# usb-cable.net
KiCad netlist of a schematic drawn in EAGLE
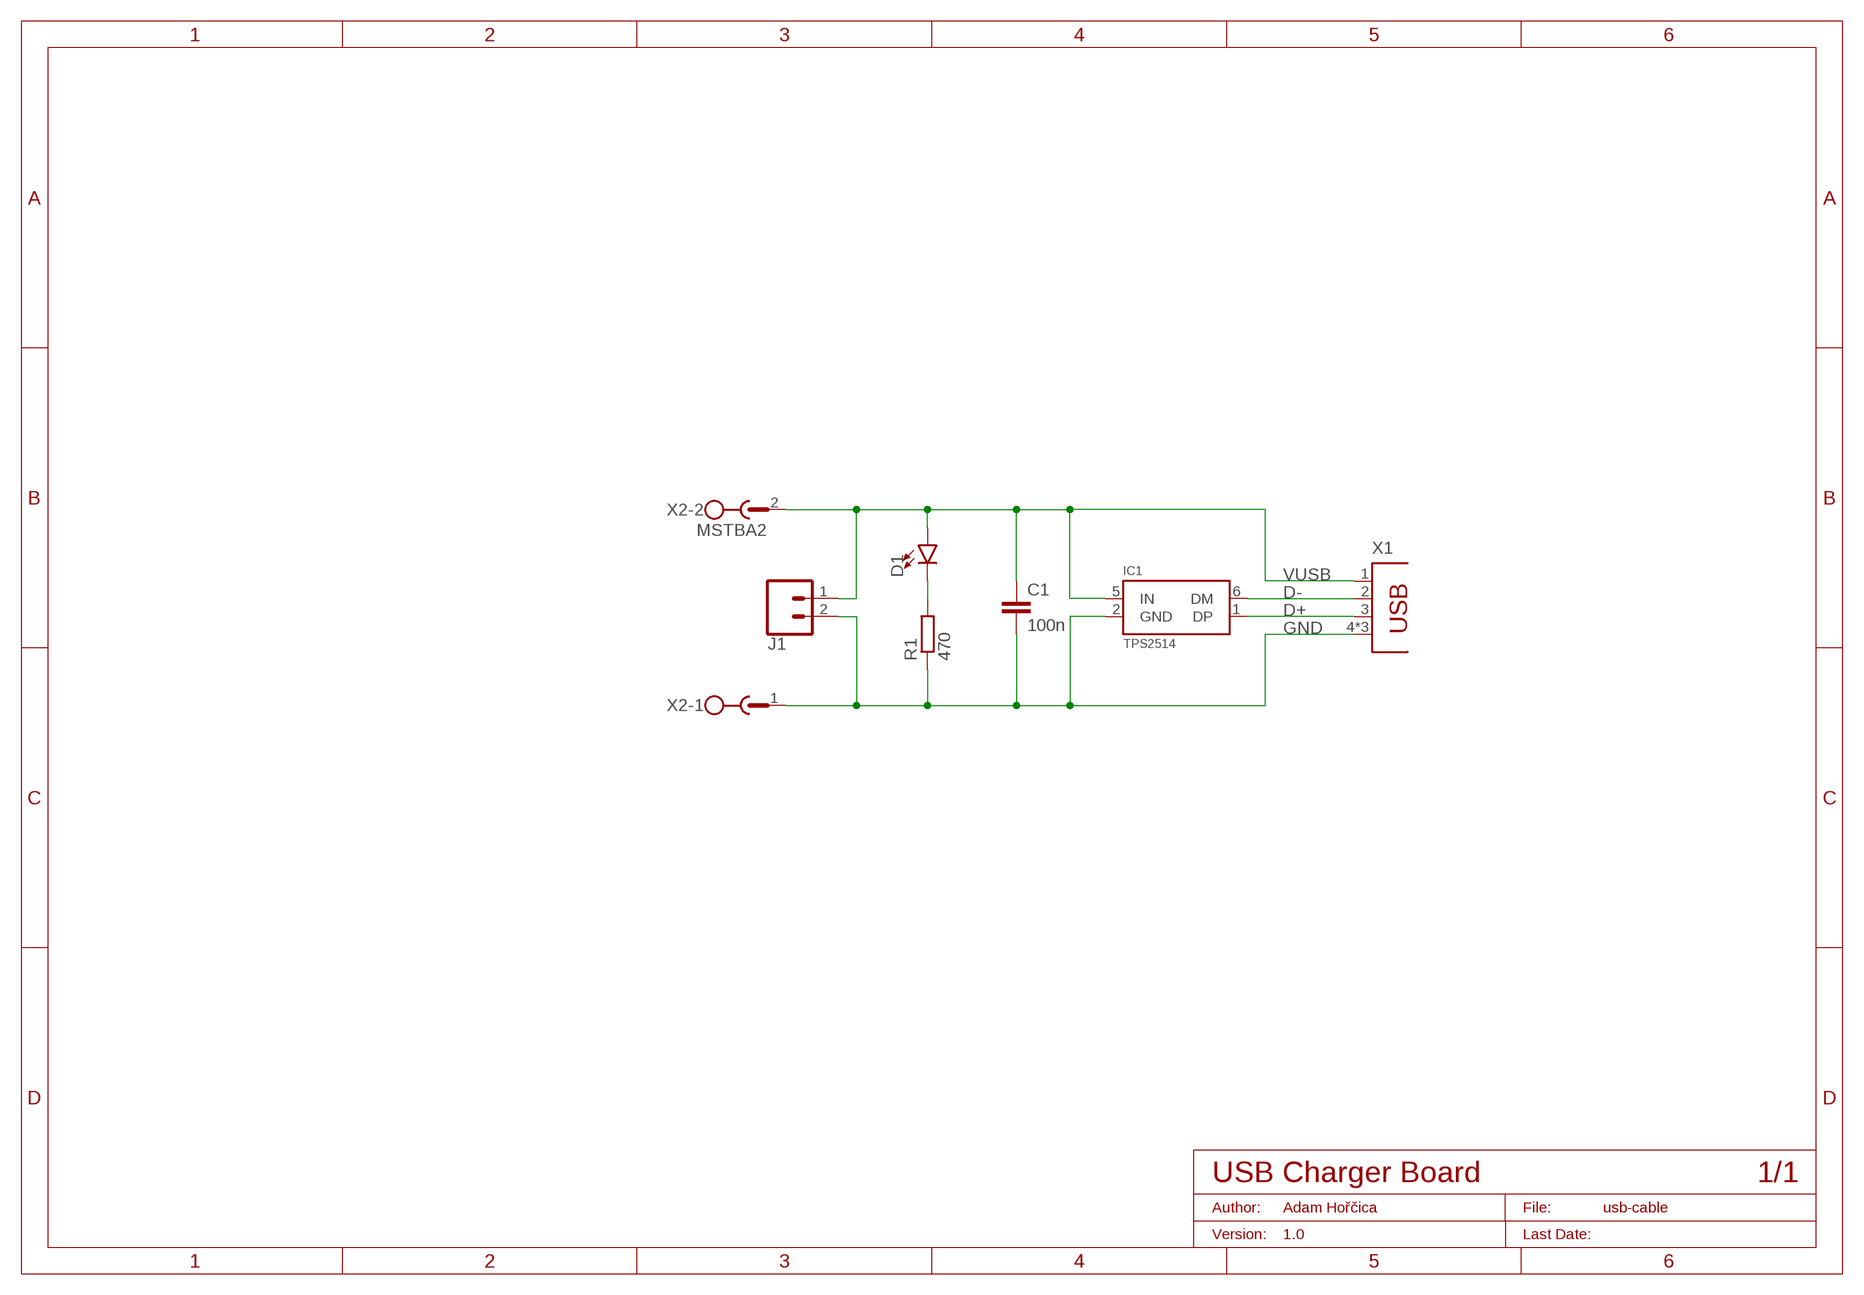
[diagram p0: schematic, sheet 1]

(export (version "E")
  (design (tool "Eeschema 10.0.6"))
  (components
    (comp (ref "C1")
      (value "100n")
      (footprint "eagle-import:C1206K")
      (libsource (lib "eagle-import") (part "C-EUC1206K"))
    )
    (comp (ref "D1")
      (value "LED0805-RESISTOR-PACKAGE")
      (footprint "eagle-import:LED-0805")
      (libsource (lib "eagle-import") (part "LED0805-RESISTOR-PACKAGE"))
    )
    (comp (ref "IC1")
      (value "TPS2514")
      (footprint "eagle-import:SOT23-6")
      (libsource (lib "eagle-import") (part "TPS2514"))
    )
    (comp (ref "J1")
      (value "CONN_02")
      (footprint "eagle-import:1X02")
      (libsource (lib "eagle-import") (part "CONN_02"))
    )
    (comp (ref "R1")
      (value "470")
      (footprint "eagle-import:R0805")
      (libsource (lib "eagle-import") (part "R-EU_R0805"))
    )
    (comp (ref "X1")
      (value "PN87520")
      (footprint "eagle-import:PN87520")
      (libsource (lib "eagle-import") (part "PN87520"))
    )
    (comp (ref "X2")
      (value "MSTBA2")
      (footprint "eagle-import:MSTBA2")
      (fields (field (name "MF") "FARNELL") (field (name "MPN") "1757242"))
      (libsource (lib "eagle-import") (part "MSTBA2"))
    )
  )
  (nets
    (net (code "1") (name "/D+") (class "Default")
      (node (ref "IC1") (pin "1") (pinfunction "DP_1") (pintype "bidirectional"))
      (node (ref "X1") (pin "3") (pinfunction "3_3") (pintype "passive"))
    )
    (net (code "2") (name "/D-") (class "Default")
      (node (ref "IC1") (pin "6") (pinfunction "DM_6") (pintype "bidirectional"))
      (node (ref "X1") (pin "2") (pinfunction "2_2") (pintype "passive"))
    )
    (net (code "3") (name "/GND") (class "Default")
      (node (ref "C1") (pin "2") (pinfunction "2_2") (pintype "passive"))
      (node (ref "IC1") (pin "2") (pinfunction "GND_2") (pintype "power_in"))
      (node (ref "J1") (pin "2") (pinfunction "2_2") (pintype "passive"))
      (node (ref "R1") (pin "1") (pinfunction "1_1") (pintype "passive"))
      (node (ref "X1") (pin "4") (pinfunction "4_4") (pintype "passive"))
      (node (ref "X1") (pin "S1") (pinfunction "4_S1") (pintype "passive"))
      (node (ref "X1") (pin "S2") (pinfunction "4_S2") (pintype "passive"))
      (node (ref "X2") (pin "1") (pinfunction "1_1") (pintype "passive"))
    )
    (net (code "4") (name "/VUSB") (class "Default")
      (node (ref "C1") (pin "1") (pinfunction "1_1") (pintype "passive"))
      (node (ref "D1") (pin "1") (pinfunction "A_1") (pintype "passive"))
      (node (ref "IC1") (pin "5") (pinfunction "IN_5") (pintype "bidirectional"))
      (node (ref "J1") (pin "1") (pinfunction "1_1") (pintype "passive"))
      (node (ref "X1") (pin "1") (pinfunction "1_1") (pintype "passive"))
      (node (ref "X2") (pin "2") (pinfunction "1_2") (pintype "passive"))
    )
    (net (code "5") (name "Net-(D1-C)") (class "Default")
      (node (ref "D1") (pin "2") (pinfunction "C_2") (pintype "passive"))
      (node (ref "R1") (pin "2") (pinfunction "2_2") (pintype "passive"))
    )
  )
)
